# rotaryfona.net
KiCad netlist of a schematic drawn in EAGLE
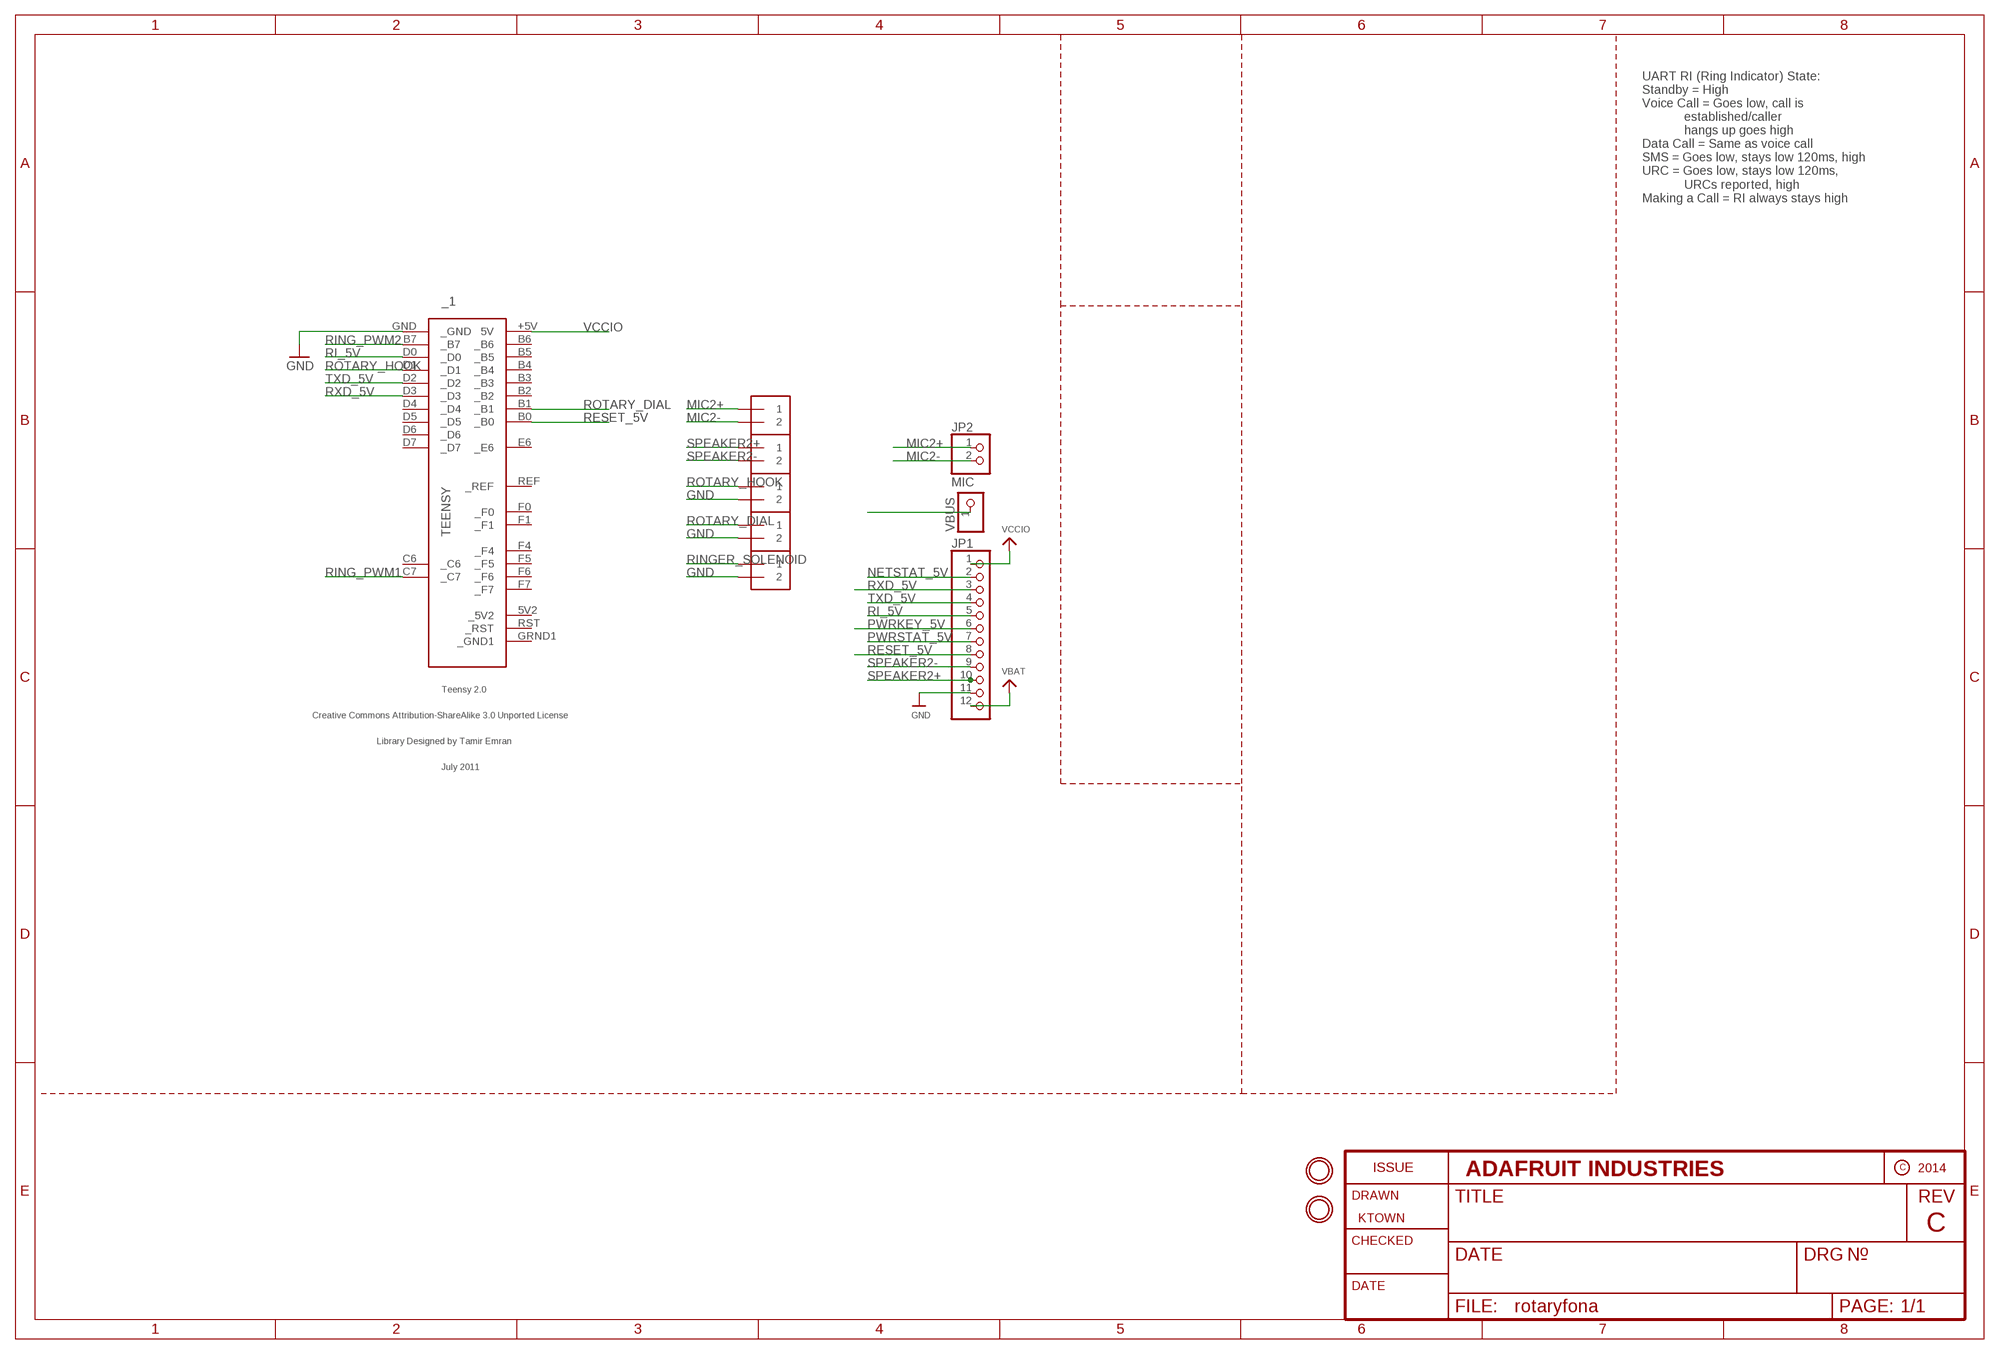
[diagram p0: schematic, sheet 1]

(export (version "E")
  (design (tool "Eeschema 10.0.6"))
  (components
    (comp (ref "DIAL")
      (value "1X2-3.5MM")
      (footprint "eagle-import:1X2-3.5MM")
      (libsource (lib "eagle-import") (part "1X2-3.5MM"))
    )
    (comp (ref "HOOK")
      (value "1X2-3.5MM")
      (footprint "eagle-import:1X2-3.5MM")
      (libsource (lib "eagle-import") (part "1X2-3.5MM"))
    )
    (comp (ref "JP1")
      (value "PINHD-1X12-CB")
      (footprint "eagle-import:1X12-CB")
      (libsource (lib "eagle-import") (part "PINHD-1X12-CB"))
    )
    (comp (ref "JP2")
      (value "MIC")
      (footprint "eagle-import:1X02_ROUND")
      (libsource (lib "eagle-import") (part "HEADER-1X2ROUND"))
    )
    (comp (ref "MIC")
      (value "1X2-3.5MM")
      (footprint "eagle-import:1X2-3.5MM")
      (libsource (lib "eagle-import") (part "1X2-3.5MM"))
    )
    (comp (ref "RINGER")
      (value "1X2-3.5MM")
      (footprint "eagle-import:1X2-3.5MM")
      (libsource (lib "eagle-import") (part "1X2-3.5MM"))
    )
    (comp (ref "SPK")
      (value "1X2-3.5MM")
      (footprint "eagle-import:1X2-3.5MM")
      (libsource (lib "eagle-import") (part "1X2-3.5MM"))
    )
    (comp (ref "U$33")
      (value "MOUNTINGHOLE2.5")
      (footprint "eagle-import:MOUNTINGHOLE_2.5_PLATED")
      (libsource (lib "eagle-import") (part "MOUNTINGHOLE2.5"))
    )
    (comp (ref "U$34")
      (value "MOUNTINGHOLE2.5")
      (footprint "eagle-import:MOUNTINGHOLE_2.5_PLATED")
      (libsource (lib "eagle-import") (part "MOUNTINGHOLE2.5"))
    )
    (comp (ref "VBUS")
      (value "PINHD-1X1CB")
      (footprint "eagle-import:1X01-CLEANBIG")
      (libsource (lib "eagle-import") (part "PINHD-1X1CB"))
    )
    (comp (ref "_1")
      (value "TEENSY")
      (footprint "eagle-import:TEENSY")
      (libsource (lib "eagle-import") (part "TEENSY"))
    )
  )
  (nets
    (net (code "1") (name "/MIC2+") (class "Default")
      (node (ref "JP2") (pin "1") (pinfunction "1_1") (pintype "passive"))
      (node (ref "MIC") (pin "1") (pinfunction "1_1") (pintype "passive"))
    )
    (net (code "2") (name "/MIC2-") (class "Default")
      (node (ref "JP2") (pin "2") (pinfunction "2_2") (pintype "passive"))
      (node (ref "MIC") (pin "2") (pinfunction "2_2") (pintype "passive"))
    )
    (net (code "3") (name "/NETSTAT_5V") (class "Default")
      (node (ref "JP1") (pin "2") (pinfunction "2_2") (pintype "passive"))
    )
    (net (code "4") (name "/PWRKEY_5V") (class "Default")
      (node (ref "JP1") (pin "6") (pinfunction "6_6") (pintype "passive"))
    )
    (net (code "5") (name "/PWRSTAT_5V") (class "Default")
      (node (ref "JP1") (pin "7") (pinfunction "7_7") (pintype "passive"))
    )
    (net (code "6") (name "/RESET_5V") (class "Default")
      (node (ref "JP1") (pin "8") (pinfunction "8_8") (pintype "passive"))
      (node (ref "_1") (pin "B0") (pinfunction "_B0_B0") (pintype "bidirectional"))
    )
    (net (code "7") (name "/RINGER_SOLENOID") (class "Default")
      (node (ref "RINGER") (pin "1") (pinfunction "1_1") (pintype "passive"))
    )
    (net (code "8") (name "/RING_PWM1") (class "Default")
      (node (ref "_1") (pin "C7") (pinfunction "_C7_C7") (pintype "bidirectional"))
    )
    (net (code "9") (name "/RING_PWM2") (class "Default")
      (node (ref "_1") (pin "B7") (pinfunction "_B7_B7") (pintype "bidirectional"))
    )
    (net (code "10") (name "/RI_5V") (class "Default")
      (node (ref "JP1") (pin "5") (pinfunction "5_5") (pintype "passive"))
      (node (ref "_1") (pin "D0") (pinfunction "_D0_D0") (pintype "bidirectional"))
    )
    (net (code "11") (name "/ROTARY_DIAL") (class "Default")
      (node (ref "DIAL") (pin "1") (pinfunction "1_1") (pintype "passive"))
      (node (ref "_1") (pin "B1") (pinfunction "_B1_B1") (pintype "bidirectional"))
    )
    (net (code "12") (name "/ROTARY_HOOK") (class "Default")
      (node (ref "HOOK") (pin "1") (pinfunction "1_1") (pintype "passive"))
      (node (ref "_1") (pin "D1") (pinfunction "_D1_D1") (pintype "bidirectional"))
    )
    (net (code "13") (name "/RXD_5V") (class "Default")
      (node (ref "JP1") (pin "3") (pinfunction "3_3") (pintype "passive"))
      (node (ref "_1") (pin "D3") (pinfunction "_D3_D3") (pintype "bidirectional"))
    )
    (net (code "14") (name "/SPEAKER2+") (class "Default")
      (node (ref "JP1") (pin "10") (pinfunction "10_10") (pintype "passive"))
      (node (ref "SPK") (pin "1") (pinfunction "1_1") (pintype "passive"))
    )
    (net (code "15") (name "/SPEAKER2-") (class "Default")
      (node (ref "JP1") (pin "9") (pinfunction "9_9") (pintype "passive"))
      (node (ref "SPK") (pin "2") (pinfunction "2_2") (pintype "passive"))
    )
    (net (code "16") (name "/TXD_5V") (class "Default")
      (node (ref "JP1") (pin "4") (pinfunction "4_4") (pintype "passive"))
      (node (ref "_1") (pin "D2") (pinfunction "_D2_D2") (pintype "bidirectional"))
    )
    (net (code "17") (name "GND") (class "Default")
      (node (ref "DIAL") (pin "2") (pinfunction "2_2") (pintype "passive"))
      (node (ref "HOOK") (pin "2") (pinfunction "2_2") (pintype "passive"))
      (node (ref "JP1") (pin "11") (pinfunction "11_11") (pintype "passive"))
      (node (ref "RINGER") (pin "2") (pinfunction "2_2") (pintype "passive"))
      (node (ref "_1") (pin "GND") (pinfunction "_GND_GND") (pintype "bidirectional"))
    )
    (net (code "18") (name "VBAT") (class "Default")
      (node (ref "JP1") (pin "12") (pinfunction "12_12") (pintype "passive"))
    )
    (net (code "19") (name "VCCIO") (class "Default")
      (node (ref "JP1") (pin "1") (pinfunction "1_1") (pintype "passive"))
      (node (ref "_1") (pin "+5V") (pinfunction "5V_+5V") (pintype "bidirectional"))
    )
    (net (code "20") (name "unconnected-(VBUS-Pad1)") (class "Default")
      (node (ref "VBUS") (pin "1") (pinfunction "1_1") (pintype "passive"))
    )
    (net (code "21") (name "unconnected-(_1-_5V2-Pad5V2)") (class "Default")
      (node (ref "_1") (pin "5V2") (pinfunction "_5V2_5V2") (pintype "bidirectional"))
    )
    (net (code "22") (name "unconnected-(_1-_B2-PadB2)") (class "Default")
      (node (ref "_1") (pin "B2") (pinfunction "_B2_B2") (pintype "bidirectional"))
    )
    (net (code "23") (name "unconnected-(_1-_B3-PadB3)") (class "Default")
      (node (ref "_1") (pin "B3") (pinfunction "_B3_B3") (pintype "bidirectional"))
    )
    (net (code "24") (name "unconnected-(_1-_B4-PadB4)") (class "Default")
      (node (ref "_1") (pin "B4") (pinfunction "_B4_B4") (pintype "bidirectional"))
    )
    (net (code "25") (name "unconnected-(_1-_B5-PadB5)") (class "Default")
      (node (ref "_1") (pin "B5") (pinfunction "_B5_B5") (pintype "bidirectional"))
    )
    (net (code "26") (name "unconnected-(_1-_B6-PadB6)") (class "Default")
      (node (ref "_1") (pin "B6") (pinfunction "_B6_B6") (pintype "bidirectional"))
    )
    (net (code "27") (name "unconnected-(_1-_C6-PadC6)") (class "Default")
      (node (ref "_1") (pin "C6") (pinfunction "_C6_C6") (pintype "bidirectional"))
    )
    (net (code "28") (name "unconnected-(_1-_D4-PadD4)") (class "Default")
      (node (ref "_1") (pin "D4") (pinfunction "_D4_D4") (pintype "bidirectional"))
    )
    (net (code "29") (name "unconnected-(_1-_D5-PadD5)") (class "Default")
      (node (ref "_1") (pin "D5") (pinfunction "_D5_D5") (pintype "bidirectional"))
    )
    (net (code "30") (name "unconnected-(_1-_D6-PadD6)") (class "Default")
      (node (ref "_1") (pin "D6") (pinfunction "_D6_D6") (pintype "bidirectional"))
    )
    (net (code "31") (name "unconnected-(_1-_D7-PadD7)") (class "Default")
      (node (ref "_1") (pin "D7") (pinfunction "_D7_D7") (pintype "bidirectional"))
    )
    (net (code "32") (name "unconnected-(_1-_E6-PadE6)") (class "Default")
      (node (ref "_1") (pin "E6") (pinfunction "_E6_E6") (pintype "bidirectional"))
    )
    (net (code "33") (name "unconnected-(_1-_F0-PadF0)") (class "Default")
      (node (ref "_1") (pin "F0") (pinfunction "_F0_F0") (pintype "bidirectional"))
    )
    (net (code "34") (name "unconnected-(_1-_F1-PadF1)") (class "Default")
      (node (ref "_1") (pin "F1") (pinfunction "_F1_F1") (pintype "bidirectional"))
    )
    (net (code "35") (name "unconnected-(_1-_F4-PadF4)") (class "Default")
      (node (ref "_1") (pin "F4") (pinfunction "_F4_F4") (pintype "bidirectional"))
    )
    (net (code "36") (name "unconnected-(_1-_F5-PadF5)") (class "Default")
      (node (ref "_1") (pin "F5") (pinfunction "_F5_F5") (pintype "bidirectional"))
    )
    (net (code "37") (name "unconnected-(_1-_F6-PadF6)") (class "Default")
      (node (ref "_1") (pin "F6") (pinfunction "_F6_F6") (pintype "bidirectional"))
    )
    (net (code "38") (name "unconnected-(_1-_F7-PadF7)") (class "Default")
      (node (ref "_1") (pin "F7") (pinfunction "_F7_F7") (pintype "bidirectional"))
    )
    (net (code "39") (name "unconnected-(_1-_GND1-PadGRND1)") (class "Default")
      (node (ref "_1") (pin "GRND1") (pinfunction "_GND1_GRND1") (pintype "bidirectional"))
    )
    (net (code "40") (name "unconnected-(_1-_REF-PadREF)") (class "Default")
      (node (ref "_1") (pin "REF") (pinfunction "_REF_REF") (pintype "bidirectional"))
    )
    (net (code "41") (name "unconnected-(_1-_RST-PadRST)") (class "Default")
      (node (ref "_1") (pin "RST") (pinfunction "_RST_RST") (pintype "bidirectional"))
    )
  )
)
